# 7__CSI.net
KiCad netlist of a schematic drawn in Altium Designer
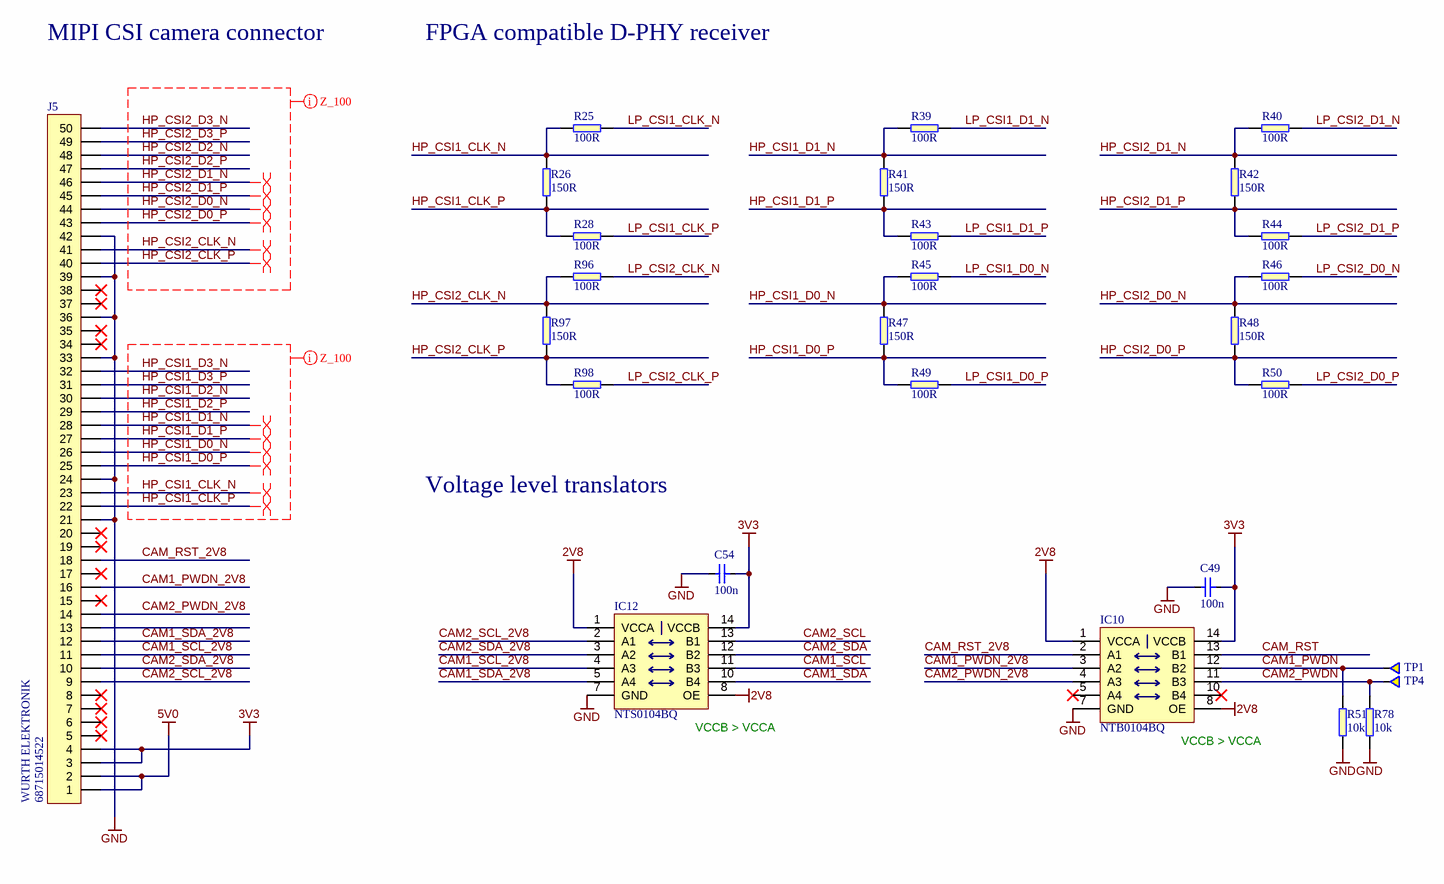
[diagram p0: [7]_CSI.SchDoc]

(export (version "E")
  (design (tool "Eeschema 10.0.6"))
  (components
    (comp (ref "C49")
      (value "100n")
      (footprint "0402")
      (description "MLCC SMT Capacitor 100nF 0402")
      (fields (field (name "PART NUMBER") "C_100n_0402") (field (name "VOLTAGE") "10V"))
      (libsource (lib "Zynq-Video-Board-Rev-1.2") (part "C_100n_0402"))
    )
    (comp (ref "C54")
      (value "100n")
      (footprint "0402")
      (description "MLCC SMT Capacitor 100nF 0402")
      (fields (field (name "PART NUMBER") "C_100n_0402") (field (name "VOLTAGE") "10V"))
      (libsource (lib "Zynq-Video-Board-Rev-1.2") (part "C_100n_0402"))
    )
    (comp (ref "IC10")
      (value "NTB0104BQ")
      (footprint "DHVQFN14")
      (description "4 bit voltage level translator - no pullups")
      (fields (field (name "MANUFACTURER") "NXP"))
      (libsource (lib "Zynq-Video-Board-Rev-1.2") (part "NTB0104BQ"))
    )
    (comp (ref "IC12")
      (value "NTS0104BQ")
      (footprint "DHVQFN14")
      (description "4 bit voltage level translator - pullups")
      (fields (field (name "MANUFACTURER") "NXP"))
      (libsource (lib "Zynq-Video-Board-Rev-1.2") (part "NTS0104BQ"))
    )
    (comp (ref "J5")
      (value "68715014522")
      (footprint "68715014522_FLIPPED")
      (description "0.50mm SMT ZIF Horizontal Bottom Contact WR-FPC")
      (fields
        (field (name "PART NUMBER") "WE-687-150-145-22_FLIPPED")
        (field (name "MANUFACTURER") "WURTH ELEKTRONIK")
      )
      (libsource (lib "Zynq-Video-Board-Rev-1.2") (part "1X50"))
    )
    (comp (ref "R25")
      (value "100R")
      (footprint "0402")
      (description "SMT Resistor 100R 0402")
      (fields (field (name "PART NUMBER") "R_100R_0402") (field (name "TOLERANCE") "1%"))
      (libsource (lib "Zynq-Video-Board-Rev-1.2") (part "R_100R_0402"))
    )
    (comp (ref "R26")
      (value "150R")
      (footprint "0402")
      (description "SMT Resistor 150R_0402")
      (fields (field (name "PART NUMBER") "R_150R_0402") (field (name "TOLERANCE") "1%"))
      (libsource (lib "Zynq-Video-Board-Rev-1.2") (part "R_150R_0402"))
    )
    (comp (ref "R28")
      (value "100R")
      (footprint "0402")
      (description "SMT Resistor 100R 0402")
      (fields (field (name "PART NUMBER") "R_100R_0402") (field (name "TOLERANCE") "1%"))
      (libsource (lib "Zynq-Video-Board-Rev-1.2") (part "R_100R_0402"))
    )
    (comp (ref "R39")
      (value "100R")
      (footprint "0402")
      (description "SMT Resistor 100R 0402")
      (fields (field (name "PART NUMBER") "R_100R_0402") (field (name "TOLERANCE") "1%"))
      (libsource (lib "Zynq-Video-Board-Rev-1.2") (part "R_100R_0402"))
    )
    (comp (ref "R40")
      (value "100R")
      (footprint "0402")
      (description "SMT Resistor 100R 0402")
      (fields (field (name "PART NUMBER") "R_100R_0402") (field (name "TOLERANCE") "1%"))
      (libsource (lib "Zynq-Video-Board-Rev-1.2") (part "R_100R_0402"))
    )
    (comp (ref "R41")
      (value "150R")
      (footprint "0402")
      (description "SMT Resistor 150R_0402")
      (fields (field (name "PART NUMBER") "R_150R_0402") (field (name "TOLERANCE") "1%"))
      (libsource (lib "Zynq-Video-Board-Rev-1.2") (part "R_150R_0402"))
    )
    (comp (ref "R42")
      (value "150R")
      (footprint "0402")
      (description "SMT Resistor 150R_0402")
      (fields (field (name "PART NUMBER") "R_150R_0402") (field (name "TOLERANCE") "1%"))
      (libsource (lib "Zynq-Video-Board-Rev-1.2") (part "R_150R_0402"))
    )
    (comp (ref "R43")
      (value "100R")
      (footprint "0402")
      (description "SMT Resistor 100R 0402")
      (fields (field (name "PART NUMBER") "R_100R_0402") (field (name "TOLERANCE") "1%"))
      (libsource (lib "Zynq-Video-Board-Rev-1.2") (part "R_100R_0402"))
    )
    (comp (ref "R44")
      (value "100R")
      (footprint "0402")
      (description "SMT Resistor 100R 0402")
      (fields (field (name "PART NUMBER") "R_100R_0402") (field (name "TOLERANCE") "1%"))
      (libsource (lib "Zynq-Video-Board-Rev-1.2") (part "R_100R_0402"))
    )
    (comp (ref "R45")
      (value "100R")
      (footprint "0402")
      (description "SMT Resistor 100R 0402")
      (fields (field (name "PART NUMBER") "R_100R_0402") (field (name "TOLERANCE") "1%"))
      (libsource (lib "Zynq-Video-Board-Rev-1.2") (part "R_100R_0402"))
    )
    (comp (ref "R46")
      (value "100R")
      (footprint "0402")
      (description "SMT Resistor 100R 0402")
      (fields (field (name "PART NUMBER") "R_100R_0402") (field (name "TOLERANCE") "1%"))
      (libsource (lib "Zynq-Video-Board-Rev-1.2") (part "R_100R_0402"))
    )
    (comp (ref "R47")
      (value "150R")
      (footprint "0402")
      (description "SMT Resistor 150R_0402")
      (fields (field (name "PART NUMBER") "R_150R_0402") (field (name "TOLERANCE") "1%"))
      (libsource (lib "Zynq-Video-Board-Rev-1.2") (part "R_150R_0402"))
    )
    (comp (ref "R48")
      (value "150R")
      (footprint "0402")
      (description "SMT Resistor 150R_0402")
      (fields (field (name "PART NUMBER") "R_150R_0402") (field (name "TOLERANCE") "1%"))
      (libsource (lib "Zynq-Video-Board-Rev-1.2") (part "R_150R_0402"))
    )
    (comp (ref "R49")
      (value "100R")
      (footprint "0402")
      (description "SMT Resistor 100R 0402")
      (fields (field (name "PART NUMBER") "R_100R_0402") (field (name "TOLERANCE") "1%"))
      (libsource (lib "Zynq-Video-Board-Rev-1.2") (part "R_100R_0402"))
    )
    (comp (ref "R50")
      (value "100R")
      (footprint "0402")
      (description "SMT Resistor 100R 0402")
      (fields (field (name "PART NUMBER") "R_100R_0402") (field (name "TOLERANCE") "1%"))
      (libsource (lib "Zynq-Video-Board-Rev-1.2") (part "R_100R_0402"))
    )
    (comp (ref "R51")
      (value "10k")
      (footprint "0402")
      (description "SMT Resistor 10k 0402")
      (fields (field (name "PART NUMBER") "R_10k_0402") (field (name "TOLERANCE") "1%"))
      (libsource (lib "Zynq-Video-Board-Rev-1.2") (part "R_10k_0402"))
    )
    (comp (ref "R78")
      (value "10k")
      (footprint "0402")
      (description "SMT Resistor 10k 0402")
      (fields (field (name "PART NUMBER") "R_10k_0402") (field (name "TOLERANCE") "1%"))
      (libsource (lib "Zynq-Video-Board-Rev-1.2") (part "R_10k_0402"))
    )
    (comp (ref "R96")
      (value "100R")
      (footprint "0402")
      (description "SMT Resistor 100R 0402")
      (fields (field (name "PART NUMBER") "R_100R_0402") (field (name "TOLERANCE") "1%"))
      (libsource (lib "Zynq-Video-Board-Rev-1.2") (part "R_100R_0402"))
    )
    (comp (ref "R97")
      (value "150R")
      (footprint "0402")
      (description "SMT Resistor 150R_0402")
      (fields (field (name "PART NUMBER") "R_150R_0402") (field (name "TOLERANCE") "1%"))
      (libsource (lib "Zynq-Video-Board-Rev-1.2") (part "R_150R_0402"))
    )
    (comp (ref "R98")
      (value "100R")
      (footprint "0402")
      (description "SMT Resistor 100R 0402")
      (fields (field (name "PART NUMBER") "R_100R_0402") (field (name "TOLERANCE") "1%"))
      (libsource (lib "Zynq-Video-Board-Rev-1.2") (part "R_100R_0402"))
    )
    (comp (ref "TP1")
      (value "Testpad")
      (footprint "TP-R-2")
      (description "Testpad, round, 2mm")
      (fields (field (name "PART NUMBER") "TP-R-2"))
      (libsource (lib "Zynq-Video-Board-Rev-1.2") (part "Testpad"))
    )
    (comp (ref "TP4")
      (value "Testpad")
      (footprint "TP-R-2")
      (description "Testpad, round, 2mm")
      (fields (field (name "PART NUMBER") "TP-R-2"))
      (libsource (lib "Zynq-Video-Board-Rev-1.2") (part "Testpad"))
    )
  )
  (nets
    (net (code "1") (name "/CAM1_PWDN") (class "Default")
      (node (ref "IC10") (pin "12") (pinfunction "B2_12") (pintype "passive"))
      (node (ref "R51") (pin "2") (pintype "passive"))
      (node (ref "TP1") (pin "1") (pintype "passive"))
    )
    (net (code "2") (name "/CAM1_PWDN_2V8") (class "Default")
      (node (ref "IC10") (pin "3") (pinfunction "A2_3") (pintype "passive"))
      (node (ref "J5") (pin "16") (pinfunction "16_16") (pintype "passive"))
    )
    (net (code "3") (name "/CAM1_SCL") (class "Default")
      (node (ref "IC12") (pin "11") (pinfunction "B3_11") (pintype "passive"))
    )
    (net (code "4") (name "/CAM1_SCL_2V8") (class "Default")
      (node (ref "IC12") (pin "4") (pinfunction "A3_4") (pintype "passive"))
      (node (ref "J5") (pin "11") (pinfunction "11_11") (pintype "passive"))
    )
    (net (code "5") (name "/CAM1_SDA") (class "Default")
      (node (ref "IC12") (pin "10") (pinfunction "B4_10") (pintype "passive"))
    )
    (net (code "6") (name "/CAM1_SDA_2V8") (class "Default")
      (node (ref "IC12") (pin "5") (pinfunction "A4_5") (pintype "passive"))
      (node (ref "J5") (pin "12") (pinfunction "12_12") (pintype "passive"))
    )
    (net (code "7") (name "/CAM2_PWDN") (class "Default")
      (node (ref "IC10") (pin "11") (pinfunction "B3_11") (pintype "passive"))
      (node (ref "R78") (pin "2") (pintype "passive"))
      (node (ref "TP4") (pin "1") (pintype "passive"))
    )
    (net (code "8") (name "/CAM2_PWDN_2V8") (class "Default")
      (node (ref "IC10") (pin "4") (pinfunction "A3_4") (pintype "passive"))
      (node (ref "J5") (pin "14") (pinfunction "14_14") (pintype "passive"))
    )
    (net (code "9") (name "/CAM2_SCL") (class "Default")
      (node (ref "IC12") (pin "13") (pinfunction "B1_13") (pintype "passive"))
    )
    (net (code "10") (name "/CAM2_SCL_2V8") (class "Default")
      (node (ref "IC12") (pin "2") (pinfunction "A1_2") (pintype "passive"))
      (node (ref "J5") (pin "9") (pinfunction "9_9") (pintype "passive"))
    )
    (net (code "11") (name "/CAM2_SDA") (class "Default")
      (node (ref "IC12") (pin "12") (pinfunction "B2_12") (pintype "passive"))
    )
    (net (code "12") (name "/CAM2_SDA_2V8") (class "Default")
      (node (ref "IC12") (pin "3") (pinfunction "A2_3") (pintype "passive"))
      (node (ref "J5") (pin "10") (pinfunction "10_10") (pintype "passive"))
    )
    (net (code "13") (name "/CAM_RST") (class "Default")
      (node (ref "IC10") (pin "13") (pinfunction "B1_13") (pintype "passive"))
    )
    (net (code "14") (name "/CAM_RST_2V8") (class "Default")
      (node (ref "IC10") (pin "2") (pinfunction "A1_2") (pintype "passive"))
      (node (ref "J5") (pin "18") (pinfunction "18_18") (pintype "passive"))
    )
    (net (code "15") (name "/HP_CSI1_CLK_N") (class "Default")
      (node (ref "J5") (pin "23") (pinfunction "23_23") (pintype "passive"))
      (node (ref "R25") (pin "1") (pintype "passive"))
      (node (ref "R26") (pin "2") (pintype "passive"))
    )
    (net (code "16") (name "/HP_CSI1_CLK_P") (class "Default")
      (node (ref "J5") (pin "22") (pinfunction "22_22") (pintype "passive"))
      (node (ref "R26") (pin "1") (pintype "passive"))
      (node (ref "R28") (pin "1") (pintype "passive"))
    )
    (net (code "17") (name "/HP_CSI1_D0_N") (class "Default")
      (node (ref "J5") (pin "26") (pinfunction "26_26") (pintype "passive"))
      (node (ref "R45") (pin "1") (pintype "passive"))
      (node (ref "R47") (pin "2") (pintype "passive"))
    )
    (net (code "18") (name "/HP_CSI1_D0_P") (class "Default")
      (node (ref "J5") (pin "25") (pinfunction "25_25") (pintype "passive"))
      (node (ref "R47") (pin "1") (pintype "passive"))
      (node (ref "R49") (pin "1") (pintype "passive"))
    )
    (net (code "19") (name "/HP_CSI1_D1_N") (class "Default")
      (node (ref "J5") (pin "28") (pinfunction "28_28") (pintype "passive"))
      (node (ref "R39") (pin "1") (pintype "passive"))
      (node (ref "R41") (pin "2") (pintype "passive"))
    )
    (net (code "20") (name "/HP_CSI1_D1_P") (class "Default")
      (node (ref "J5") (pin "27") (pinfunction "27_27") (pintype "passive"))
      (node (ref "R41") (pin "1") (pintype "passive"))
      (node (ref "R43") (pin "1") (pintype "passive"))
    )
    (net (code "21") (name "/HP_CSI1_D2_N") (class "Default")
      (node (ref "J5") (pin "30") (pinfunction "30_30") (pintype "passive"))
    )
    (net (code "22") (name "/HP_CSI1_D2_P") (class "Default")
      (node (ref "J5") (pin "29") (pinfunction "29_29") (pintype "passive"))
    )
    (net (code "23") (name "/HP_CSI1_D3_N") (class "Default")
      (node (ref "J5") (pin "32") (pinfunction "32_32") (pintype "passive"))
    )
    (net (code "24") (name "/HP_CSI1_D3_P") (class "Default")
      (node (ref "J5") (pin "31") (pinfunction "31_31") (pintype "passive"))
    )
    (net (code "25") (name "/HP_CSI2_CLK_N") (class "Default")
      (node (ref "J5") (pin "41") (pinfunction "41_41") (pintype "passive"))
      (node (ref "R96") (pin "1") (pintype "passive"))
      (node (ref "R97") (pin "2") (pintype "passive"))
    )
    (net (code "26") (name "/HP_CSI2_CLK_P") (class "Default")
      (node (ref "J5") (pin "40") (pinfunction "40_40") (pintype "passive"))
      (node (ref "R97") (pin "1") (pintype "passive"))
      (node (ref "R98") (pin "1") (pintype "passive"))
    )
    (net (code "27") (name "/HP_CSI2_D0_N") (class "Default")
      (node (ref "J5") (pin "44") (pinfunction "44_44") (pintype "passive"))
      (node (ref "R46") (pin "1") (pintype "passive"))
      (node (ref "R48") (pin "2") (pintype "passive"))
    )
    (net (code "28") (name "/HP_CSI2_D0_P") (class "Default")
      (node (ref "J5") (pin "43") (pinfunction "43_43") (pintype "passive"))
      (node (ref "R48") (pin "1") (pintype "passive"))
      (node (ref "R50") (pin "1") (pintype "passive"))
    )
    (net (code "29") (name "/HP_CSI2_D1_N") (class "Default")
      (node (ref "J5") (pin "46") (pinfunction "46_46") (pintype "passive"))
      (node (ref "R40") (pin "1") (pintype "passive"))
      (node (ref "R42") (pin "2") (pintype "passive"))
    )
    (net (code "30") (name "/HP_CSI2_D1_P") (class "Default")
      (node (ref "J5") (pin "45") (pinfunction "45_45") (pintype "passive"))
      (node (ref "R42") (pin "1") (pintype "passive"))
      (node (ref "R44") (pin "1") (pintype "passive"))
    )
    (net (code "31") (name "/HP_CSI2_D2_N") (class "Default")
      (node (ref "J5") (pin "48") (pinfunction "48_48") (pintype "passive"))
    )
    (net (code "32") (name "/HP_CSI2_D2_P") (class "Default")
      (node (ref "J5") (pin "47") (pinfunction "47_47") (pintype "passive"))
    )
    (net (code "33") (name "/HP_CSI2_D3_N") (class "Default")
      (node (ref "J5") (pin "50") (pinfunction "50_50") (pintype "passive"))
    )
    (net (code "34") (name "/HP_CSI2_D3_P") (class "Default")
      (node (ref "J5") (pin "49") (pinfunction "49_49") (pintype "passive"))
    )
    (net (code "35") (name "/LP_CSI1_CLK_N") (class "Default")
      (node (ref "R25") (pin "2") (pintype "passive"))
    )
    (net (code "36") (name "/LP_CSI1_CLK_P") (class "Default")
      (node (ref "R28") (pin "2") (pintype "passive"))
    )
    (net (code "37") (name "/LP_CSI1_D0_N") (class "Default")
      (node (ref "R45") (pin "2") (pintype "passive"))
    )
    (net (code "38") (name "/LP_CSI1_D0_P") (class "Default")
      (node (ref "R49") (pin "2") (pintype "passive"))
    )
    (net (code "39") (name "/LP_CSI1_D1_N") (class "Default")
      (node (ref "R39") (pin "2") (pintype "passive"))
    )
    (net (code "40") (name "/LP_CSI1_D1_P") (class "Default")
      (node (ref "R43") (pin "2") (pintype "passive"))
    )
    (net (code "41") (name "/LP_CSI2_CLK_N") (class "Default")
      (node (ref "R96") (pin "2") (pintype "passive"))
    )
    (net (code "42") (name "/LP_CSI2_CLK_P") (class "Default")
      (node (ref "R98") (pin "2") (pintype "passive"))
    )
    (net (code "43") (name "/LP_CSI2_D0_N") (class "Default")
      (node (ref "R46") (pin "2") (pintype "passive"))
    )
    (net (code "44") (name "/LP_CSI2_D0_P") (class "Default")
      (node (ref "R50") (pin "2") (pintype "passive"))
    )
    (net (code "45") (name "/LP_CSI2_D1_N") (class "Default")
      (node (ref "R40") (pin "2") (pintype "passive"))
    )
    (net (code "46") (name "/LP_CSI2_D1_P") (class "Default")
      (node (ref "R44") (pin "2") (pintype "passive"))
    )
    (net (code "47") (name "2V8") (class "Default")
      (node (ref "IC10") (pin "1") (pinfunction "VCCA_1") (pintype "passive"))
      (node (ref "IC10") (pin "8") (pinfunction "OE_8") (pintype "passive"))
      (node (ref "IC12") (pin "1") (pinfunction "VCCA_1") (pintype "passive"))
      (node (ref "IC12") (pin "8") (pinfunction "OE_8") (pintype "passive"))
    )
    (net (code "48") (name "3V3") (class "Default")
      (node (ref "C49") (pin "1") (pinfunction "1_1") (pintype "passive"))
      (node (ref "C54") (pin "1") (pinfunction "1_1") (pintype "passive"))
      (node (ref "IC10") (pin "14") (pinfunction "VCCB_14") (pintype "passive"))
      (node (ref "IC12") (pin "14") (pinfunction "VCCB_14") (pintype "passive"))
      (node (ref "J5") (pin "3") (pinfunction "3_3") (pintype "passive"))
      (node (ref "J5") (pin "4") (pinfunction "4_4") (pintype "passive"))
    )
    (net (code "49") (name "5V0") (class "Default")
      (node (ref "J5") (pin "1") (pinfunction "1_1") (pintype "passive"))
      (node (ref "J5") (pin "2") (pinfunction "2_2") (pintype "passive"))
    )
    (net (code "50") (name "GND") (class "Default")
      (node (ref "C49") (pin "2") (pinfunction "2_2") (pintype "passive"))
      (node (ref "C54") (pin "2") (pinfunction "2_2") (pintype "passive"))
      (node (ref "IC10") (pin "7") (pinfunction "GND_7") (pintype "passive"))
      (node (ref "IC12") (pin "7") (pinfunction "GND_7") (pintype "passive"))
      (node (ref "J5") (pin "21") (pinfunction "21_21") (pintype "passive"))
      (node (ref "J5") (pin "24") (pinfunction "24_24") (pintype "passive"))
      (node (ref "J5") (pin "33") (pinfunction "33_33") (pintype "passive"))
      (node (ref "J5") (pin "36") (pinfunction "36_36") (pintype "passive"))
      (node (ref "J5") (pin "39") (pinfunction "39_39") (pintype "passive"))
      (node (ref "J5") (pin "42") (pinfunction "42_42") (pintype "passive"))
      (node (ref "R51") (pin "1") (pintype "passive"))
      (node (ref "R78") (pin "1") (pintype "passive"))
    )
    (net (code "51") (name "unconnected-(IC10-A4-Pad5)") (class "Default")
      (node (ref "IC10") (pin "5") (pinfunction "A4_5") (pintype "passive+no_connect"))
    )
    (net (code "52") (name "unconnected-(IC10-B4-Pad10)") (class "Default")
      (node (ref "IC10") (pin "10") (pinfunction "B4_10") (pintype "passive+no_connect"))
    )
    (net (code "53") (name "unconnected-(J5-Pad5)") (class "Default")
      (node (ref "J5") (pin "5") (pinfunction "5_5") (pintype "passive+no_connect"))
    )
    (net (code "54") (name "unconnected-(J5-Pad6)") (class "Default")
      (node (ref "J5") (pin "6") (pinfunction "6_6") (pintype "passive+no_connect"))
    )
    (net (code "55") (name "unconnected-(J5-Pad7)") (class "Default")
      (node (ref "J5") (pin "7") (pinfunction "7_7") (pintype "passive+no_connect"))
    )
    (net (code "56") (name "unconnected-(J5-Pad8)") (class "Default")
      (node (ref "J5") (pin "8") (pinfunction "8_8") (pintype "passive+no_connect"))
    )
    (net (code "57") (name "unconnected-(J5-Pad13)") (class "Default")
      (node (ref "J5") (pin "13") (pinfunction "13_13") (pintype "passive"))
    )
    (net (code "58") (name "unconnected-(J5-Pad15)") (class "Default")
      (node (ref "J5") (pin "15") (pinfunction "15_15") (pintype "passive+no_connect"))
    )
    (net (code "59") (name "unconnected-(J5-Pad17)") (class "Default")
      (node (ref "J5") (pin "17") (pinfunction "17_17") (pintype "passive+no_connect"))
    )
    (net (code "60") (name "unconnected-(J5-Pad19)") (class "Default")
      (node (ref "J5") (pin "19") (pinfunction "19_19") (pintype "passive+no_connect"))
    )
    (net (code "61") (name "unconnected-(J5-Pad20)") (class "Default")
      (node (ref "J5") (pin "20") (pinfunction "20_20") (pintype "passive+no_connect"))
    )
    (net (code "62") (name "unconnected-(J5-Pad34)") (class "Default")
      (node (ref "J5") (pin "34") (pinfunction "34_34") (pintype "passive+no_connect"))
    )
    (net (code "63") (name "unconnected-(J5-Pad35)") (class "Default")
      (node (ref "J5") (pin "35") (pinfunction "35_35") (pintype "passive+no_connect"))
    )
    (net (code "64") (name "unconnected-(J5-Pad37)") (class "Default")
      (node (ref "J5") (pin "37") (pinfunction "37_37") (pintype "passive+no_connect"))
    )
    (net (code "65") (name "unconnected-(J5-Pad38)") (class "Default")
      (node (ref "J5") (pin "38") (pinfunction "38_38") (pintype "passive+no_connect"))
    )
  )
)
